# PAGE1-MAIN.net
KiCad netlist of a schematic drawn in Altium Designer
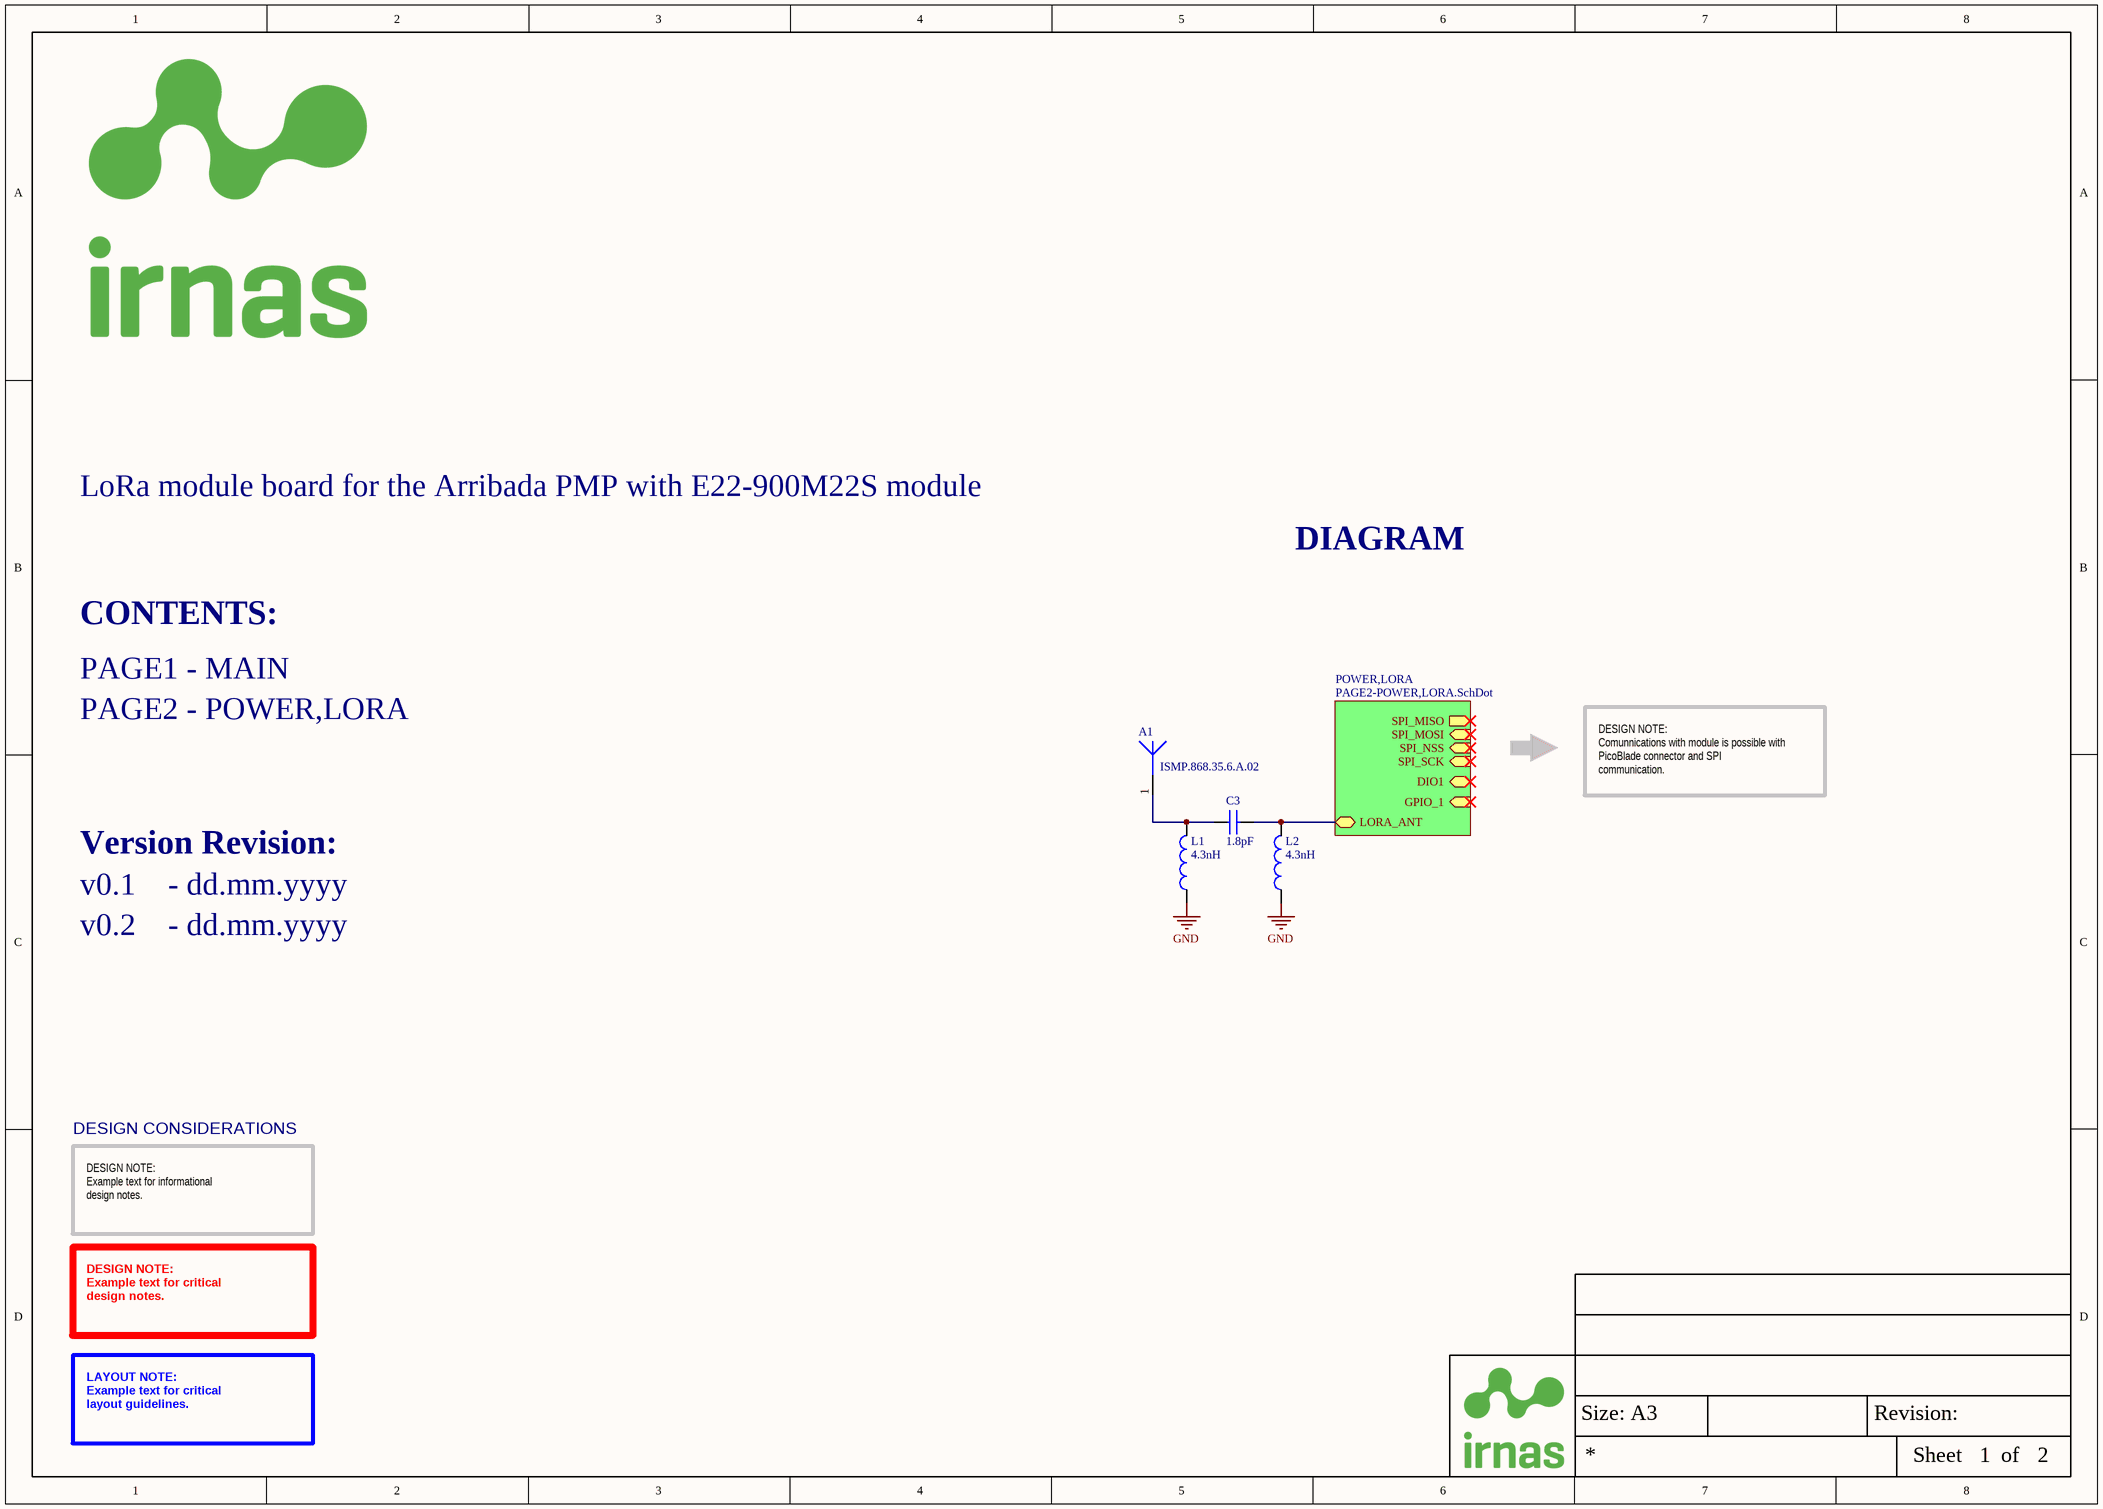
[diagram p0: PAGE1-MAIN.SchDoc]

(export (version "E")
  (design (tool "Eeschema 10.0.6"))
  (components
    (comp (ref "A1")
      (value "ISMP.868.35.6.A.02")
      (footprint "ISMP.868.35.6.A.02")
      (description "Patch Antenna, 868MHz, 2.17dBi Gain, 50ohm, Right Hand Circular Polarisation, Adhesive/Pin")
      (fields (field (name "MANUFACTURER") "Antenova") (field (name "MANUFACTURER PART NUMBER") "SR42I010-R"))
      (libsource (lib "Passive") (part "ANT - ISMP.868.35.6.A.02"))
    )
    (comp (ref "C3")
      (value "1.8pF")
      (footprint "CAP0402")
      (description "Multilayer Ceramic Capacitors MLCC - SMD/SMT 50volts 1.8pF C0G")
      (fields
        (field (name "MANUFACTURER") "KEMET")
        (field (name "MANUFACTURER PART NUMBER") "C0402C189B5GACTU")
      )
      (libsource (lib "Passive") (part "C - 1.8pF/0402"))
    )
    (comp (ref "L1")
      (value "4.3nH")
      (footprint "IND0402")
      (description "Inductor RF Chip Multi-Layer 4.3nH 0.3nH 100MHz 8Q-Factor Air 300mA 210mOhm DCR 0402 Paper T/R")
      (fields
        (field (name "MANUFACTURER") "Murata")
        (field (name "MANUFACTURER PART NUMBER") "LQG15HN4N3S02D")
      )
      (libsource (lib "Passive") (part "L - 4.3nH/0402"))
    )
    (comp (ref "L2")
      (value "4.3nH")
      (footprint "IND0402")
      (description "Inductor RF Chip Multi-Layer 4.3nH 0.3nH 100MHz 8Q-Factor Air 300mA 210mOhm DCR 0402 Paper T/R")
      (fields
        (field (name "MANUFACTURER") "Murata")
        (field (name "MANUFACTURER PART NUMBER") "LQG15HN4N3S02D")
      )
      (libsource (lib "Passive") (part "L - 4.3nH/0402"))
    )
  )
  (nets
    (net (code "3") (name "/LORA_ANT") (class "Default")
      (node (ref "C3") (pin "2") (pinfunction "2_2") (pintype "passive"))
      (node (ref "L2") (pin "2") (pinfunction "2_2") (pintype "passive"))
    )
    (net (code "8") (name "GND") (class "Default")
      (node (ref "L1") (pin "1") (pinfunction "1_1") (pintype "passive"))
      (node (ref "L2") (pin "1") (pinfunction "1_1") (pintype "passive"))
    )
    (net (code "9") (name "Net-(A1-ANT)") (class "Default")
      (node (ref "A1") (pin "1") (pinfunction "ANT_1") (pintype "passive"))
      (node (ref "C3") (pin "1") (pinfunction "1_1") (pintype "passive"))
      (node (ref "L1") (pin "2") (pinfunction "2_2") (pintype "passive"))
    )
  )
)
